# 06_Power_Supply.net
KiCad netlist of a schematic drawn in Altium Designer
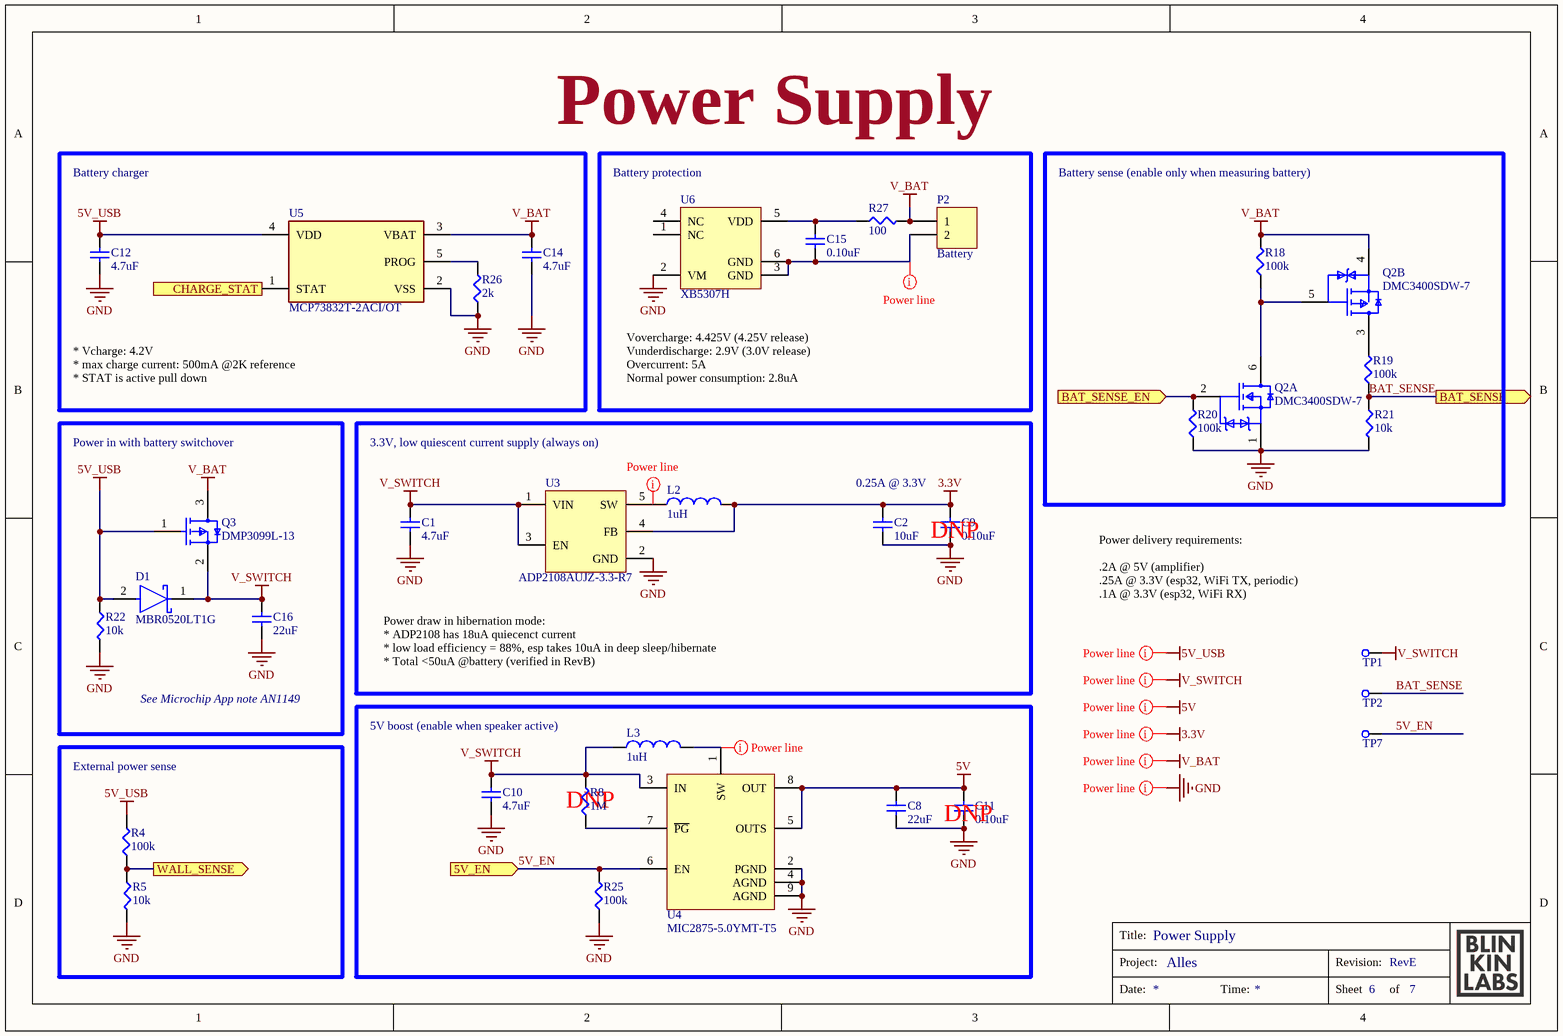
[diagram p0: [06] Power Supply.SchDoc]

(export (version "E")
  (design (tool "Eeschema 10.0.6"))
  (components
    (comp (ref "C1")
      (value "4.7uF")
      (footprint "CAPC1608X09L")
      (description "CAP CER 4.7UF 10V X5R 0603")
      (fields
        (field (name "PARTNUMBER") "GRM188R61A475KE15D")
        (field (name "DIGI-KEY PART NUMBER") "490-10477-1-ND")
      )
      (libsource (lib "cap_murata") (part "CAPACITOR"))
    )
    (comp (ref "C2")
      (value "10uF")
      (footprint "CAPC1608X09L")
      (description "CAP CER 10UF 10V X5R 0603")
      (fields
        (field (name "PARTNUMBER") "GRM188R61A106KE69D")
        (field (name "DIGI-KEY PART NUMBER") "490-10474-1-ND")
      )
      (libsource (lib "cap_murata") (part "CAPACITOR"))
    )
    (comp (ref "C8")
      (value "22uF")
      (footprint "CAPC1608X09L")
      (description "CAP CER 22UF 10V X5R 0603")
      (fields
        (field (name "PARTNUMBER") "GRM187R61A226ME15D")
        (field (name "DIGI-KEY PART NUMBER") "490-13243-1-ND")
      )
      (libsource (lib "cap_murata") (part "CAPACITOR"))
    )
    (comp (ref "C9")
      (value "0.10uF")
      (footprint "CAPC1005X06L")
      (description "CAP CER 0.1UF 16V X5R 0402")
      (fields
        (field (name "PARTNUMBER") "GRM155R61C104KA88J")
        (field (name "DIGI-KEY PART NUMBER") "490-6310-1-ND")
      )
      (libsource (lib "cap_murata") (part "CAPACITOR"))
    )
    (comp (ref "C10")
      (value "4.7uF")
      (footprint "CAPC1608X09L")
      (description "CAP CER 4.7UF 10V X5R 0603")
      (fields
        (field (name "PARTNUMBER") "GRM188R61A475KE15D")
        (field (name "DIGI-KEY PART NUMBER") "490-10477-1-ND")
      )
      (libsource (lib "cap_murata") (part "CAPACITOR"))
    )
    (comp (ref "C11")
      (value "0.10uF")
      (footprint "CAPC1005X06L")
      (description "CAP CER 0.1UF 16V X5R 0402")
      (fields
        (field (name "PARTNUMBER") "GRM155R61C104KA88J")
        (field (name "DIGI-KEY PART NUMBER") "490-6310-1-ND")
      )
      (libsource (lib "cap_murata") (part "CAPACITOR"))
    )
    (comp (ref "C12")
      (value "4.7uF")
      (footprint "CAPC1608X09L")
      (description "CAP CER 4.7UF 10V X5R 0603")
      (fields
        (field (name "PARTNUMBER") "GRM188R61A475KE15D")
        (field (name "DIGI-KEY PART NUMBER") "490-10477-1-ND")
      )
      (libsource (lib "cap_murata") (part "CAPACITOR"))
    )
    (comp (ref "C14")
      (value "4.7uF")
      (footprint "CAPC1608X09L")
      (description "CAP CER 4.7UF 10V X5R 0603")
      (fields
        (field (name "PARTNUMBER") "GRM188R61A475KE15D")
        (field (name "DIGI-KEY PART NUMBER") "490-10477-1-ND")
      )
      (libsource (lib "cap_murata") (part "CAPACITOR"))
    )
    (comp (ref "C15")
      (value "0.10uF")
      (footprint "CAPC1005X06L")
      (description "CAP CER 0.1UF 16V X5R 0402")
      (fields
        (field (name "PARTNUMBER") "GRM155R61C104KA88J")
        (field (name "DIGI-KEY PART NUMBER") "490-6310-1-ND")
      )
      (libsource (lib "cap_murata") (part "CAPACITOR"))
    )
    (comp (ref "C16")
      (value "22uF")
      (footprint "CAPC1608X09L")
      (description "CAP CER 22UF 10V X5R 0603")
      (fields
        (field (name "PARTNUMBER") "GRM187R61A226ME15D")
        (field (name "DIGI-KEY PART NUMBER") "490-13243-1-ND")
      )
      (libsource (lib "cap_murata") (part "CAPACITOR"))
    )
    (comp (ref "D1")
      (value "MBR0520LT1G")
      (footprint "FP-425-04-IPC_C")
      (description "DIODE SCHOTTKY 20V 500MA SOD123")
      (libsource (lib "Altium Content Vault") (part "1d6ec82d83fb6aee721767c19dac4b9"))
    )
    (comp (ref "L2")
      (value "1uH")
      (footprint "FNR201610S")
      (description "1uH ±20% 1.45A 114mΩ SMD,2.0x1.6x1.0mm Power Inductors RoHS")
      (fields (field (name "PARTNUMBER") "FNR201610S1R0MT") (field (name "LCSC PARTNUMBER") "C167670"))
      (libsource (lib "inductor_changjiang") (part "INDUCTOR"))
    )
    (comp (ref "L3")
      (value "1uH")
      (footprint "FNR201610S")
      (description "1uH ±20% 1.45A 114mΩ SMD,2.0x1.6x1.0mm Power Inductors RoHS")
      (fields (field (name "PARTNUMBER") "FNR201610S1R0MT") (field (name "LCSC PARTNUMBER") "C167670"))
      (libsource (lib "inductor_changjiang") (part "INDUCTOR"))
    )
    (comp (ref "P2")
      (value "Battery")
      (footprint "HDR1X2")
      (description "Header, 2-Pin")
      (fields (field (name "PUBLISHER") "Altium Limited"))
      (libsource (lib "Miscellaneous Connectors") (part "Header 2"))
    )
    (comp (ref "Q2")
      (value "DMC3400SDW-7")
      (footprint "FP-SOT363-MFG")
      (description "MOSFET N/P-CH 30V SOT363")
      (fields
        (field (name "MANUFACTURER") "Diodes Inc.")
        (field (name "OCTOPART") "https://octopart.com/dmc3400sdw-7-diodes+inc.-57605013")
      )
      (libsource (lib "Altium Content Vault") (part "35add492f2e9950036e2904eec90320"))
    )
    (comp (ref "Q3")
      (value "DMP3099L-13")
      (footprint "FP-SOT23-IPC_A")
      (description "MOSFET P-CH 30V 3.8A SOT23")
      (libsource (lib "Altium Content Vault") (part "638227d500694eacab38e5d89898fd4"))
    )
    (comp (ref "R4")
      (value "100k")
      (footprint "ERJ2G(0402)_L")
      (description "RES SMD 100K OHM 5% 1/10W 0402")
      (fields (field (name "PARTNUMBER") "ERJ-2GEJ104X") (field (name "DIGI-KEY PART NUMBER") "P100KJCT-ND"))
      (libsource (lib "res_panasonic_erj_xls") (part "RESISTOR"))
    )
    (comp (ref "R5")
      (value "10k")
      (footprint "ERJ2G(0402)_L")
      (description "RES SMD 10K OHM 5% 1/10W 0402")
      (fields (field (name "PARTNUMBER") "ERJ-2GEJ103X") (field (name "DIGI-KEY PART NUMBER") "P10KJCT-ND"))
      (libsource (lib "res_panasonic_erj_xls") (part "RESISTOR"))
    )
    (comp (ref "R8")
      (value "1M")
      (footprint "ERJ2G(0402)_L")
      (description "RES SMD 1M OHM 5% 1/10W 0402")
      (fields (field (name "PARTNUMBER") "ERJ-2GEJ105X") (field (name "DIGI-KEY PART NUMBER") "P1.0MJCT-ND"))
      (libsource (lib "res_panasonic_erj_xls") (part "RESISTOR"))
    )
    (comp (ref "R18")
      (value "100k")
      (footprint "ERJ2G(0402)_L")
      (description "RES SMD 100K OHM 5% 1/10W 0402")
      (fields (field (name "PARTNUMBER") "ERJ-2GEJ104X") (field (name "DIGI-KEY PART NUMBER") "P100KJCT-ND"))
      (libsource (lib "res_panasonic_erj_xls") (part "RESISTOR"))
    )
    (comp (ref "R19")
      (value "100k")
      (footprint "ERJ2G(0402)_L")
      (description "RES SMD 100K OHM 5% 1/10W 0402")
      (fields (field (name "PARTNUMBER") "ERJ-2GEJ104X") (field (name "DIGI-KEY PART NUMBER") "P100KJCT-ND"))
      (libsource (lib "res_panasonic_erj_xls") (part "RESISTOR"))
    )
    (comp (ref "R20")
      (value "100k")
      (footprint "ERJ2G(0402)_L")
      (description "RES SMD 100K OHM 5% 1/10W 0402")
      (fields (field (name "PARTNUMBER") "ERJ-2GEJ104X") (field (name "DIGI-KEY PART NUMBER") "P100KJCT-ND"))
      (libsource (lib "res_panasonic_erj_xls") (part "RESISTOR"))
    )
    (comp (ref "R21")
      (value "10k")
      (footprint "ERJ2G(0402)_L")
      (description "RES SMD 10K OHM 5% 1/10W 0402")
      (fields (field (name "PARTNUMBER") "ERJ-2GEJ103X") (field (name "DIGI-KEY PART NUMBER") "P10KJCT-ND"))
      (libsource (lib "res_panasonic_erj_xls") (part "RESISTOR"))
    )
    (comp (ref "R22")
      (value "10k")
      (footprint "ERJ2G(0402)_L")
      (description "RES SMD 10K OHM 5% 1/10W 0402")
      (fields (field (name "PARTNUMBER") "ERJ-2GEJ103X") (field (name "DIGI-KEY PART NUMBER") "P10KJCT-ND"))
      (libsource (lib "res_panasonic_erj_xls") (part "RESISTOR"))
    )
    (comp (ref "R25")
      (value "100k")
      (footprint "ERJ2G(0402)_L")
      (description "RES SMD 100K OHM 5% 1/10W 0402")
      (fields (field (name "PARTNUMBER") "ERJ-2GEJ104X") (field (name "DIGI-KEY PART NUMBER") "P100KJCT-ND"))
      (libsource (lib "res_panasonic_erj_xls") (part "RESISTOR"))
    )
    (comp (ref "R26")
      (value "2k")
      (footprint "ERJ2G(0402)_L")
      (description "RES SMD 2K OHM 5% 1/10W 0402")
      (fields (field (name "PARTNUMBER") "ERJ-2GEJ202X") (field (name "DIGI-KEY PART NUMBER") "P2.0KJCT-ND"))
      (libsource (lib "res_panasonic_erj_xls") (part "RESISTOR"))
    )
    (comp (ref "R27")
      (value "100")
      (footprint "ERJ2G(0402)_L")
      (description "RES SMD 100 OHM 1% 1/10W 0402")
      (fields (field (name "PARTNUMBER") "ERJ-2RKF1000X") (field (name "DIGI-KEY PART NUMBER") "P100LCT-ND"))
      (libsource (lib "res_panasonic_erj_xls") (part "RESISTOR"))
    )
    (comp (ref "TP1")
      (value "TEST_POINT")
      (footprint "TP-SMD-1mm")
      (description "Test point")
      (libsource (lib "Blinkinlabs") (part "TEST_POINT"))
    )
    (comp (ref "TP2")
      (value "TEST_POINT")
      (footprint "TP-SMD-1mm")
      (description "Test point")
      (libsource (lib "Blinkinlabs") (part "TEST_POINT"))
    )
    (comp (ref "TP7")
      (value "TEST_POINT")
      (footprint "TP-SMD-1mm")
      (description "Test point")
      (libsource (lib "Blinkinlabs") (part "TEST_POINT"))
    )
    (comp (ref "U3")
      (value "ADP2108AUJZ-3.3-R7")
      (footprint "SOT95P280X100-5N")
      (description "Compact, 600 mA, 3 MHz, Step-Down DC-to-DC Converter, 3.3V")
      (fields
        (field (name "DIGIKEY PARTNUMBER") "ADP2108AUJZ-3.3-R7CT-ND")
        (field (name "LCSC PARTNUMBER") "C143875")
      )
      (libsource (lib "Blinkinlabs") (part "ADP2108AUJZ-3.3-R7"))
    )
    (comp (ref "U4")
      (value "MIC2875-5.0YMT-T5")
      (footprint "TDFN22-8LD-PL-1 (hand drawn)")
      (description "4.8A ISW, Synchronous Boost Regulator with Bi-Directional Load Disconnect")
      (fields
        (field (name "MANUFACTURER") "Microchip")
        (field (name "DIGIKEY PARTNUMBER") "MIC2875-5.0YMT-T5CT-ND")
      )
      (libsource (lib "Blinkinlabs") (part "MIC2875-5.0YMT-T5"))
    )
    (comp (ref "U5")
      (value "MCP73832T-2ACI/OT")
      (footprint "FP-C04-091-OT-MFG")
      (description "IC LI-ION/LI-POLY CTRLR SOT23-5")
      (libsource (lib "Altium Content Vault") (part "61f5a3bb3429d9e0caadea342aa3b19"))
    )
    (comp (ref "U6")
      (value "XB5307H")
      (footprint "SOT95P280X125-6N-3")
      (description "Single-cell Li-ion/Li-polymer rechargeable battery pack protection chip w2.90V cutorff")
      (fields (field (name "MANUFACTURER") "XySemi") (field (name "LCSC PARTNUMBER") "C154942"))
      (libsource (lib "Blinkinlabs") (part "XB5307H"))
    )
  )
  (nets
    (net (code "1") (name "/5V_EN") (class "Default")
      (node (ref "R25") (pin "2") (pinfunction "2_2") (pintype "passive"))
      (node (ref "TP7") (pin "1") (pinfunction "TP_1") (pintype "passive"))
      (node (ref "U4") (pin "6") (pinfunction "EN_6") (pintype "passive"))
    )
    (net (code "2") (name "/BAT_SENSE") (class "Default")
      (node (ref "R19") (pin "1") (pinfunction "1_1") (pintype "passive"))
      (node (ref "R21") (pin "1") (pinfunction "1_1") (pintype "passive"))
      (node (ref "TP2") (pin "1") (pinfunction "TP_1") (pintype "passive"))
    )
    (net (code "3") (name "/BAT_SENSE_EN") (class "Default")
      (node (ref "Q2") (pin "2") (pinfunction "G1_2") (pintype "passive"))
      (node (ref "R20") (pin "2") (pinfunction "2_2") (pintype "passive"))
    )
    (net (code "4") (name "/CHARGE_STAT") (class "Default")
      (node (ref "U5") (pin "1") (pinfunction "STAT_1") (pintype "passive"))
    )
    (net (code "5") (name "/WALL_SENSE") (class "Default")
      (node (ref "R4") (pin "1") (pinfunction "1_1") (pintype "passive"))
      (node (ref "R5") (pin "1") (pinfunction "1_1") (pintype "passive"))
    )
    (net (code "6") (name "3.3V") (class "Default")
      (node (ref "C2") (pin "1") (pinfunction "1_1") (pintype "passive"))
      (node (ref "C9") (pin "2") (pinfunction "2_2") (pintype "passive"))
      (node (ref "L2") (pin "2") (pinfunction "2_2") (pintype "passive"))
      (node (ref "U3") (pin "4") (pinfunction "FB_4") (pintype "passive"))
    )
    (net (code "7") (name "5V") (class "Default")
      (node (ref "C11") (pin "2") (pinfunction "2_2") (pintype "passive"))
      (node (ref "C8") (pin "1") (pinfunction "1_1") (pintype "passive"))
      (node (ref "U4") (pin "5") (pinfunction "OUTS_5") (pintype "passive"))
      (node (ref "U4") (pin "8") (pinfunction "OUT_8") (pintype "passive"))
    )
    (net (code "8") (name "5V_USB") (class "Default")
      (node (ref "C12") (pin "1") (pinfunction "1_1") (pintype "passive"))
      (node (ref "D1") (pin "2") (pinfunction "A_2") (pintype "passive"))
      (node (ref "Q3") (pin "1") (pinfunction "G_1") (pintype "passive"))
      (node (ref "R22") (pin "1") (pinfunction "1_1") (pintype "passive"))
      (node (ref "R4") (pin "2") (pinfunction "2_2") (pintype "passive"))
      (node (ref "U5") (pin "4") (pinfunction "VDD_4") (pintype "power_in"))
    )
    (net (code "9") (name "GND") (class "Default")
      (node (ref "C1") (pin "2") (pinfunction "2_2") (pintype "passive"))
      (node (ref "C10") (pin "2") (pinfunction "2_2") (pintype "passive"))
      (node (ref "C11") (pin "1") (pinfunction "1_1") (pintype "passive"))
      (node (ref "C12") (pin "2") (pinfunction "2_2") (pintype "passive"))
      (node (ref "C14") (pin "2") (pinfunction "2_2") (pintype "passive"))
      (node (ref "C16") (pin "2") (pinfunction "2_2") (pintype "passive"))
      (node (ref "C2") (pin "2") (pinfunction "2_2") (pintype "passive"))
      (node (ref "C8") (pin "2") (pinfunction "2_2") (pintype "passive"))
      (node (ref "C9") (pin "1") (pinfunction "1_1") (pintype "passive"))
      (node (ref "Q2") (pin "1") (pinfunction "S1_1") (pintype "passive"))
      (node (ref "R20") (pin "1") (pinfunction "1_1") (pintype "passive"))
      (node (ref "R21") (pin "2") (pinfunction "2_2") (pintype "passive"))
      (node (ref "R22") (pin "2") (pinfunction "2_2") (pintype "passive"))
      (node (ref "R25") (pin "1") (pinfunction "1_1") (pintype "passive"))
      (node (ref "R26") (pin "1") (pinfunction "1_1") (pintype "passive"))
      (node (ref "R5") (pin "2") (pinfunction "2_2") (pintype "passive"))
      (node (ref "U3") (pin "2") (pinfunction "GND_2") (pintype "passive"))
      (node (ref "U4") (pin "2") (pinfunction "PGND_2") (pintype "passive"))
      (node (ref "U4") (pin "4") (pinfunction "AGND_4") (pintype "passive"))
      (node (ref "U4") (pin "9") (pinfunction "AGND_9") (pintype "passive"))
      (node (ref "U5") (pin "2") (pinfunction "VSS_2") (pintype "power_in"))
      (node (ref "U6") (pin "2") (pinfunction "VM_2") (pintype "passive"))
    )
    (net (code "10") (name "Net-(C15-Pad1)") (class "Default")
      (node (ref "C15") (pin "1") (pinfunction "1_1") (pintype "passive"))
      (node (ref "P2") (pin "2") (pinfunction "2_2") (pintype "passive"))
      (node (ref "U6") (pin "3") (pinfunction "GND_3") (pintype "passive"))
      (node (ref "U6") (pin "6") (pinfunction "GND_6") (pintype "passive"))
    )
    (net (code "11") (name "Net-(Q2A-D1)") (class "Default")
      (node (ref "Q2") (pin "5") (pinfunction "G2_5") (pintype "passive"))
      (node (ref "Q2") (pin "6") (pinfunction "D1_6") (pintype "passive"))
      (node (ref "R18") (pin "1") (pinfunction "1_1") (pintype "passive"))
    )
    (net (code "12") (name "Net-(Q2B-D2)") (class "Default")
      (node (ref "Q2") (pin "3") (pinfunction "D2_3") (pintype "passive"))
      (node (ref "R19") (pin "2") (pinfunction "2_2") (pintype "passive"))
    )
    (net (code "13") (name "Net-(U3-SW)") (class "Default")
      (node (ref "L2") (pin "1") (pinfunction "1_1") (pintype "passive"))
      (node (ref "U3") (pin "5") (pinfunction "SW_5") (pintype "passive"))
    )
    (net (code "14") (name "Net-(U4-SW)") (class "Default")
      (node (ref "L3") (pin "2") (pinfunction "2_2") (pintype "passive"))
      (node (ref "U4") (pin "1") (pinfunction "SW_1") (pintype "passive"))
    )
    (net (code "15") (name "Net-(U4-~{PG})") (class "Default")
      (node (ref "R8") (pin "1") (pinfunction "1_1") (pintype "passive"))
      (node (ref "U4") (pin "7") (pinfunction "~{PG}_7") (pintype "passive"))
    )
    (net (code "16") (name "Net-(U5-PROG)") (class "Default")
      (node (ref "R26") (pin "2") (pinfunction "2_2") (pintype "passive"))
      (node (ref "U5") (pin "5") (pinfunction "PROG_5") (pintype "passive"))
    )
    (net (code "17") (name "Net-(U6-VDD)") (class "Default")
      (node (ref "C15") (pin "2") (pinfunction "2_2") (pintype "passive"))
      (node (ref "R27") (pin "1") (pinfunction "1_1") (pintype "passive"))
      (node (ref "U6") (pin "5") (pinfunction "VDD_5") (pintype "passive"))
    )
    (net (code "18") (name "V_BAT") (class "Default")
      (node (ref "C14") (pin "1") (pinfunction "1_1") (pintype "passive"))
      (node (ref "P2") (pin "1") (pinfunction "1_1") (pintype "passive"))
      (node (ref "Q2") (pin "4") (pinfunction "S2_4") (pintype "passive"))
      (node (ref "Q3") (pin "3") (pinfunction "D_3") (pintype "passive"))
      (node (ref "R18") (pin "2") (pinfunction "2_2") (pintype "passive"))
      (node (ref "R27") (pin "2") (pinfunction "2_2") (pintype "passive"))
      (node (ref "U5") (pin "3") (pinfunction "VBAT_3") (pintype "power_in"))
    )
    (net (code "19") (name "V_SWITCH") (class "Default")
      (node (ref "C1") (pin "1") (pinfunction "1_1") (pintype "passive"))
      (node (ref "C10") (pin "1") (pinfunction "1_1") (pintype "passive"))
      (node (ref "C16") (pin "1") (pinfunction "1_1") (pintype "passive"))
      (node (ref "D1") (pin "1") (pinfunction "C_1") (pintype "passive"))
      (node (ref "L3") (pin "1") (pinfunction "1_1") (pintype "passive"))
      (node (ref "Q3") (pin "2") (pinfunction "S_2") (pintype "passive"))
      (node (ref "R8") (pin "2") (pinfunction "2_2") (pintype "passive"))
      (node (ref "TP1") (pin "1") (pinfunction "TP_1") (pintype "passive"))
      (node (ref "U3") (pin "1") (pinfunction "VIN_1") (pintype "passive"))
      (node (ref "U3") (pin "3") (pinfunction "EN_3") (pintype "passive"))
      (node (ref "U4") (pin "3") (pinfunction "IN_3") (pintype "passive"))
    )
    (net (code "20") (name "unconnected-(U6-NC-Pad1)") (class "Default")
      (node (ref "U6") (pin "1") (pinfunction "NC_1") (pintype "passive"))
    )
    (net (code "21") (name "unconnected-(U6-NC-Pad4)") (class "Default")
      (node (ref "U6") (pin "4") (pinfunction "NC_4") (pintype "passive"))
    )
  )
)
